# USB_HUB1.net
KiCad netlist of a schematic drawn in Altium Designer
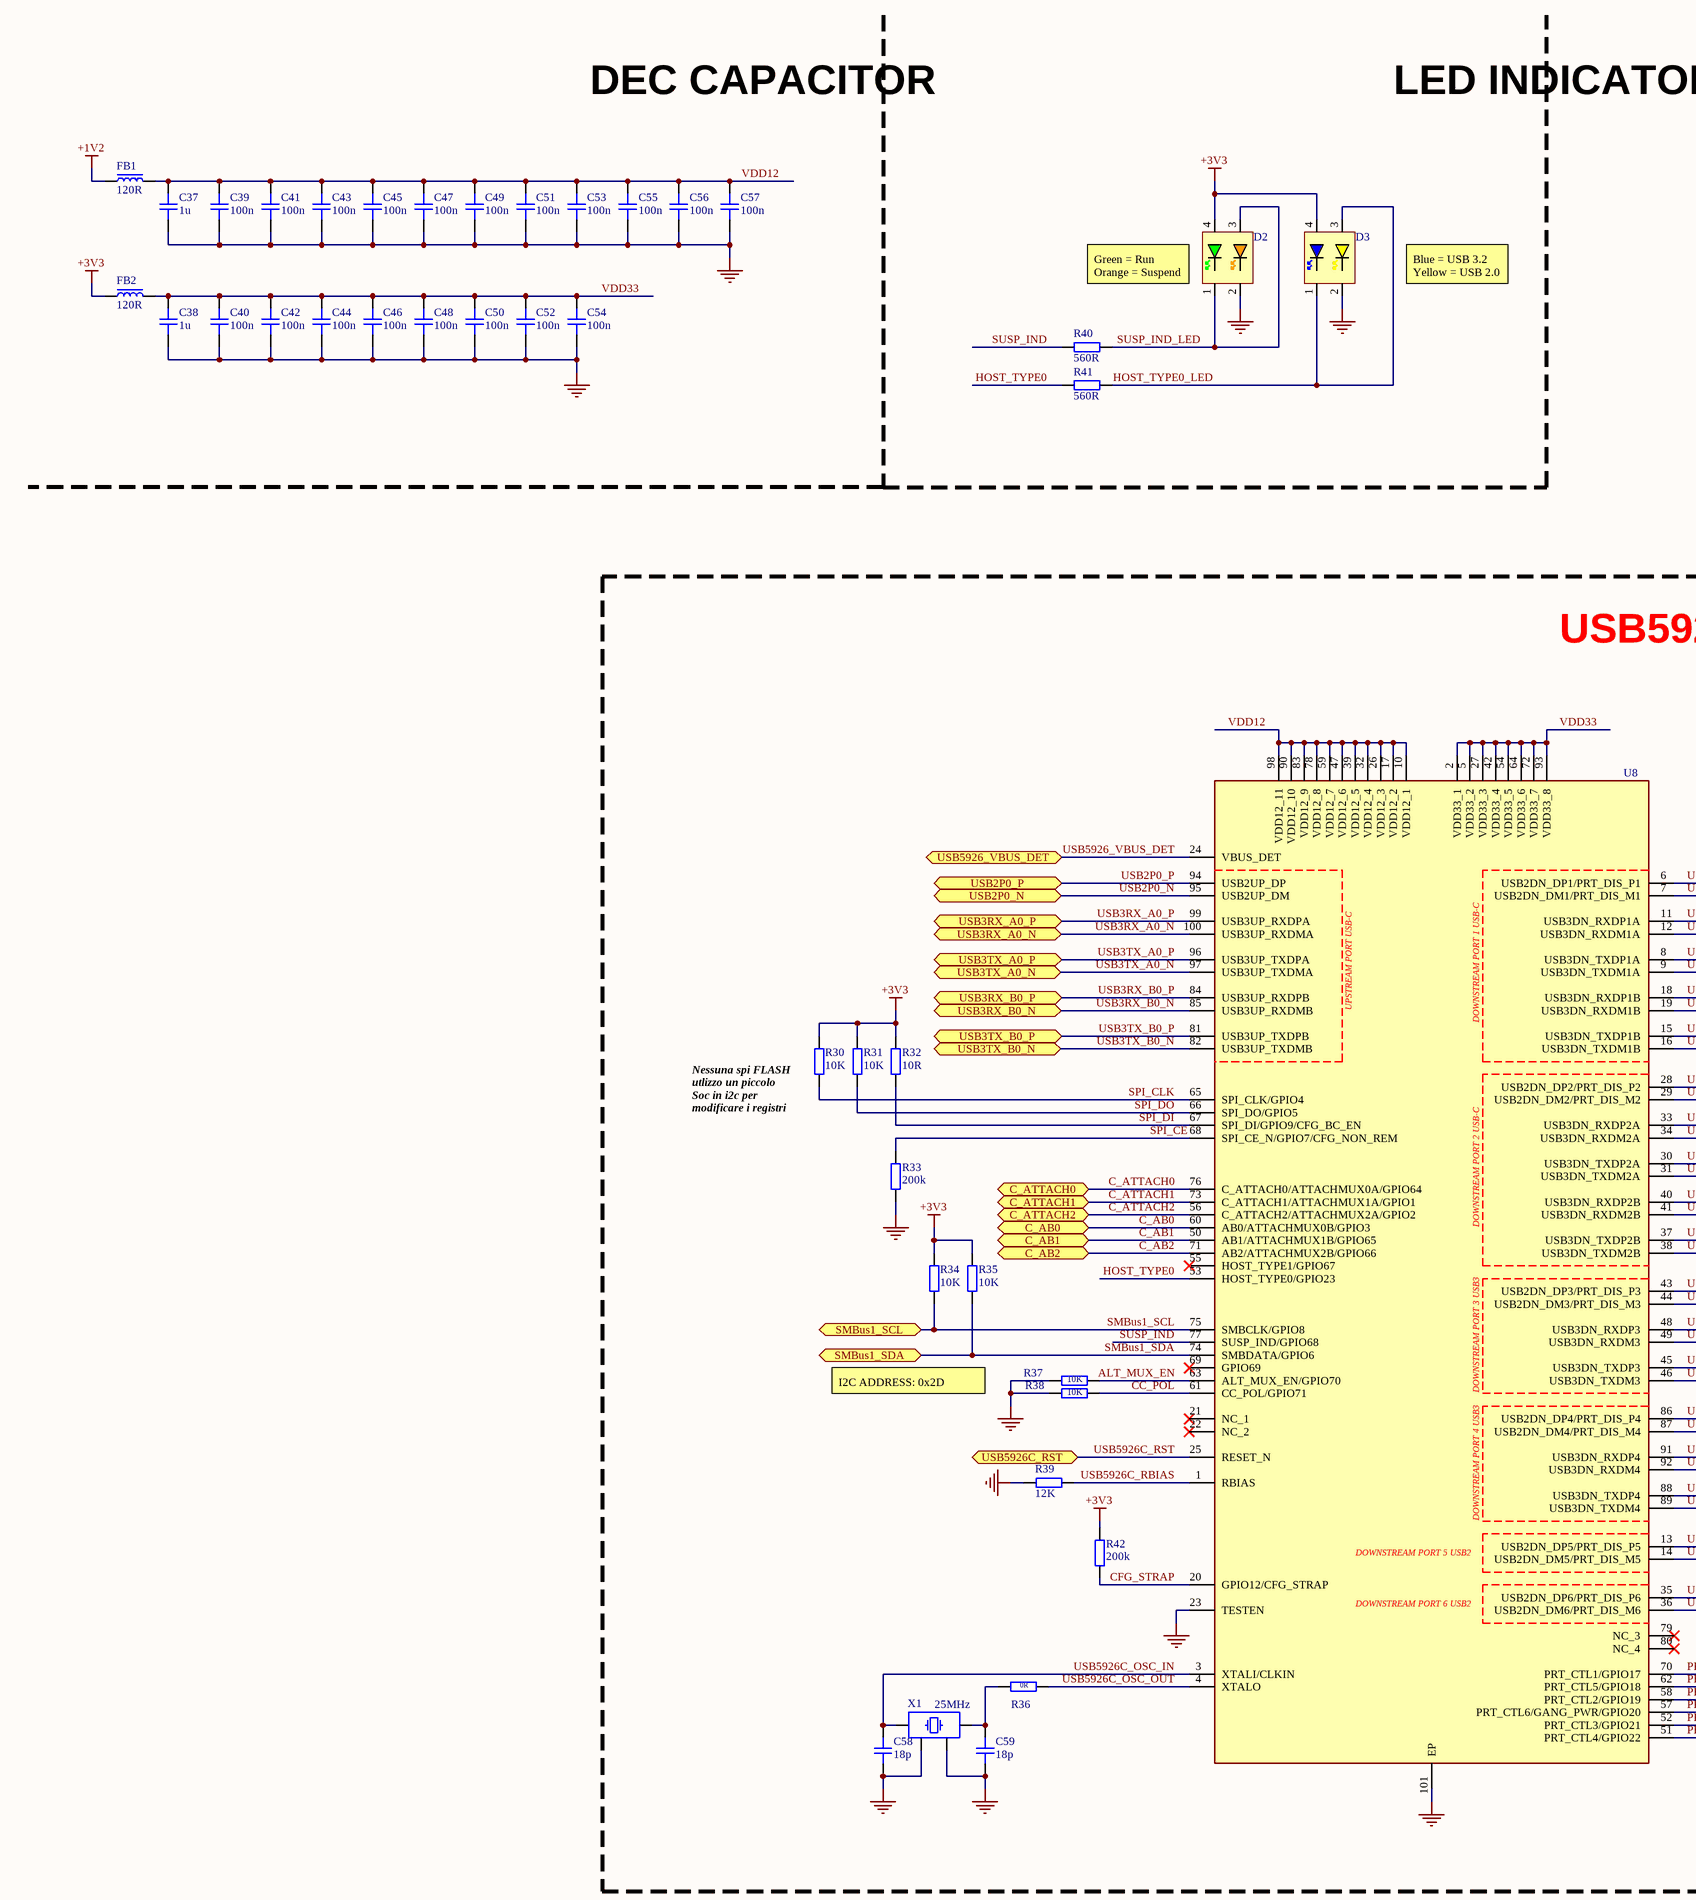
[diagram p0: USB_HUB1.SchDoc, left]
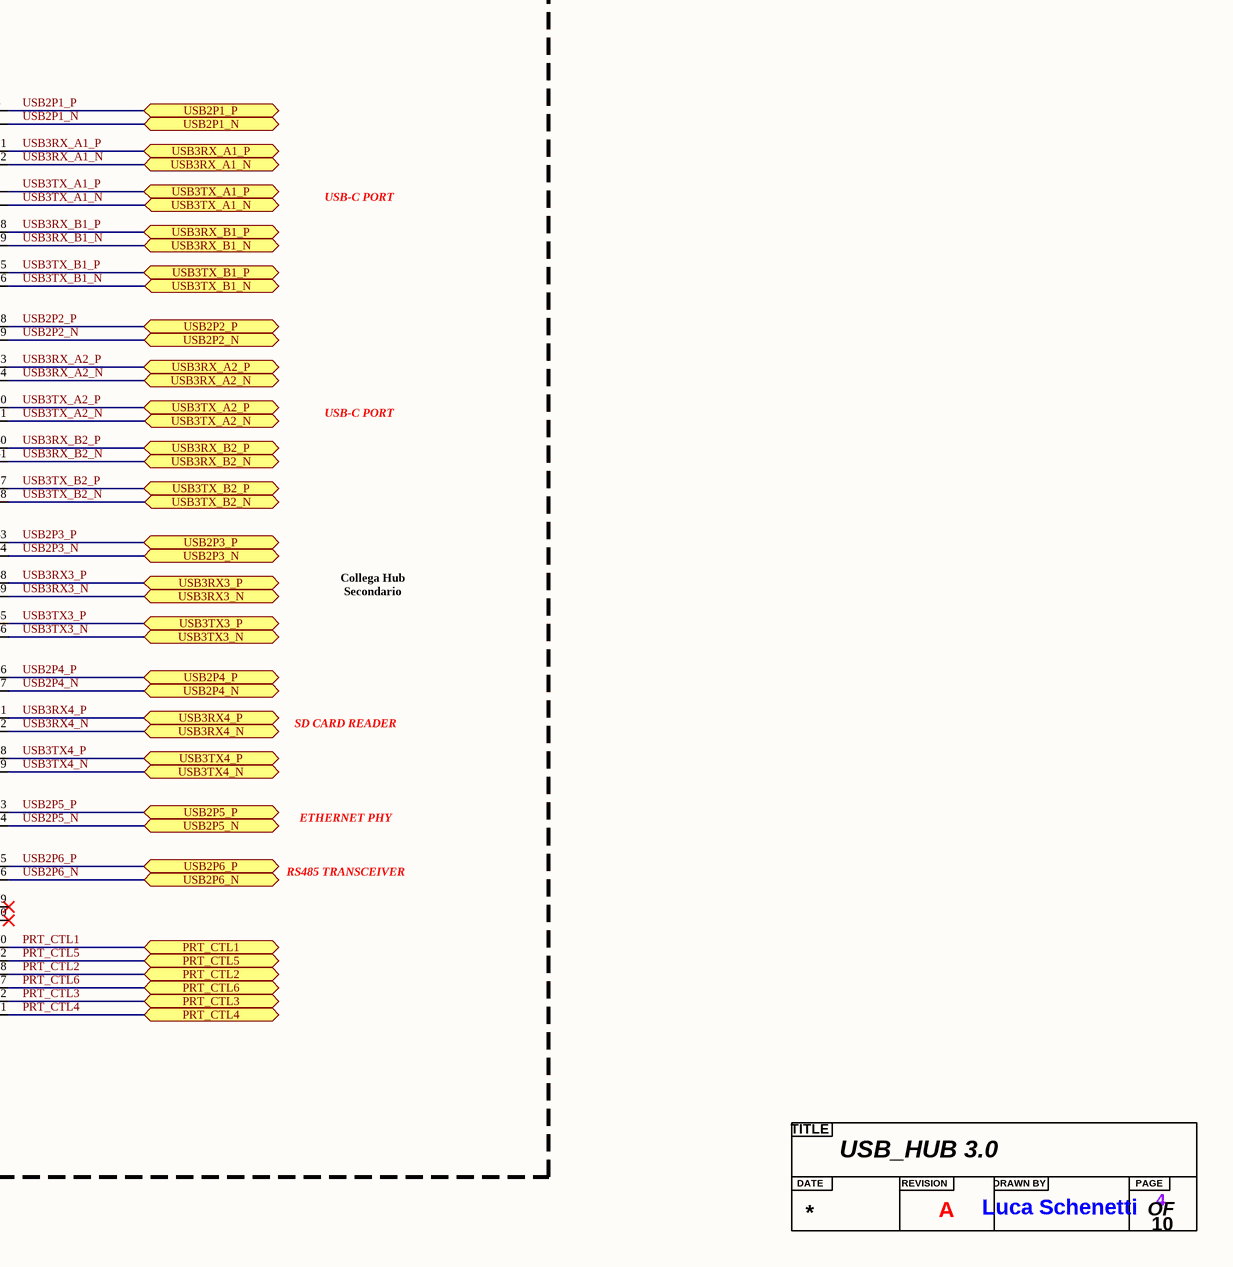
[diagram p1: USB_HUB1.SchDoc, right]

(export (version "E")
  (design (tool "Eeschema 10.0.6"))
  (components
    (comp (ref "C37")
      (value "1u")
      (footprint "CAP_0603")
      (description "Capacitor SMD 0603 [C15849]")
      (libsource (lib "Schematic-Lib-PhilsLab") (part "CAP_0603"))
    )
    (comp (ref "C38")
      (value "1u")
      (footprint "CAP_0603")
      (description "Capacitor SMD 0603 [C15849]")
      (libsource (lib "Schematic-Lib-PhilsLab") (part "CAP_0603"))
    )
    (comp (ref "C39")
      (value "100n")
      (footprint "CAP_0603")
      (description "Capacitor SMD 0603 [C14663]")
      (libsource (lib "Schematic-Lib-PhilsLab") (part "CAP_0603"))
    )
    (comp (ref "C40")
      (value "100n")
      (footprint "CAP_0603")
      (description "Capacitor SMD 0603 [C14663]")
      (libsource (lib "Schematic-Lib-PhilsLab") (part "CAP_0603"))
    )
    (comp (ref "C41")
      (value "100n")
      (footprint "CAP_0603")
      (description "Capacitor SMD 0603 [C14663]")
      (libsource (lib "Schematic-Lib-PhilsLab") (part "CAP_0603"))
    )
    (comp (ref "C42")
      (value "100n")
      (footprint "CAP_0603")
      (description "Capacitor SMD 0603 [C14663]")
      (libsource (lib "Schematic-Lib-PhilsLab") (part "CAP_0603"))
    )
    (comp (ref "C43")
      (value "100n")
      (footprint "CAP_0603")
      (description "Capacitor SMD 0603 [C14663]")
      (libsource (lib "Schematic-Lib-PhilsLab") (part "CAP_0603"))
    )
    (comp (ref "C44")
      (value "100n")
      (footprint "CAP_0603")
      (description "Capacitor SMD 0603 [C14663]")
      (libsource (lib "Schematic-Lib-PhilsLab") (part "CAP_0603"))
    )
    (comp (ref "C45")
      (value "100n")
      (footprint "CAP_0603")
      (description "Capacitor SMD 0603 [C14663]")
      (libsource (lib "Schematic-Lib-PhilsLab") (part "CAP_0603"))
    )
    (comp (ref "C46")
      (value "100n")
      (footprint "CAP_0603")
      (description "Capacitor SMD 0603 [C14663]")
      (libsource (lib "Schematic-Lib-PhilsLab") (part "CAP_0603"))
    )
    (comp (ref "C47")
      (value "100n")
      (footprint "CAP_0603")
      (description "Capacitor SMD 0603 [C14663]")
      (libsource (lib "Schematic-Lib-PhilsLab") (part "CAP_0603"))
    )
    (comp (ref "C48")
      (value "100n")
      (footprint "CAP_0603")
      (description "Capacitor SMD 0603 [C14663]")
      (libsource (lib "Schematic-Lib-PhilsLab") (part "CAP_0603"))
    )
    (comp (ref "C49")
      (value "100n")
      (footprint "CAP_0603")
      (description "Capacitor SMD 0603 [C14663]")
      (libsource (lib "Schematic-Lib-PhilsLab") (part "CAP_0603"))
    )
    (comp (ref "C50")
      (value "100n")
      (footprint "CAP_0603")
      (description "Capacitor SMD 0603 [C14663]")
      (libsource (lib "Schematic-Lib-PhilsLab") (part "CAP_0603"))
    )
    (comp (ref "C51")
      (value "100n")
      (footprint "CAP_0603")
      (description "Capacitor SMD 0603 [C14663]")
      (libsource (lib "Schematic-Lib-PhilsLab") (part "CAP_0603"))
    )
    (comp (ref "C52")
      (value "100n")
      (footprint "CAP_0603")
      (description "Capacitor SMD 0603 [C14663]")
      (libsource (lib "Schematic-Lib-PhilsLab") (part "CAP_0603"))
    )
    (comp (ref "C53")
      (value "100n")
      (footprint "CAP_0603")
      (description "Capacitor SMD 0603 [C14663]")
      (libsource (lib "Schematic-Lib-PhilsLab") (part "CAP_0603"))
    )
    (comp (ref "C54")
      (value "100n")
      (footprint "CAP_0603")
      (description "Capacitor SMD 0603 [C14663]")
      (libsource (lib "Schematic-Lib-PhilsLab") (part "CAP_0603"))
    )
    (comp (ref "C55")
      (value "100n")
      (footprint "CAP_0603")
      (description "Capacitor SMD 0603 [C14663]")
      (libsource (lib "Schematic-Lib-PhilsLab") (part "CAP_0603"))
    )
    (comp (ref "C56")
      (value "100n")
      (footprint "CAP_0603")
      (description "Capacitor SMD 0603 [C14663]")
      (libsource (lib "Schematic-Lib-PhilsLab") (part "CAP_0603"))
    )
    (comp (ref "C57")
      (value "100n")
      (footprint "CAP_0603")
      (description "Capacitor SMD 0603 [C14663]")
      (libsource (lib "Schematic-Lib-PhilsLab") (part "CAP_0603"))
    )
    (comp (ref "C58")
      (value "18p")
      (footprint "CAP_0402")
      (description "Capacitor SMD 0402 [C1549]")
      (libsource (lib "Schematic-Lib-PhilsLab") (part "CAP_0402"))
    )
    (comp (ref "C59")
      (value "18p")
      (footprint "CAP_0402")
      (description "Capacitor SMD 0402 [C1549]")
      (libsource (lib "Schematic-Lib-PhilsLab") (part "CAP_0402"))
    )
    (comp (ref "D2")
      (value "TWO LED Orange Green 0603")
      (footprint "A-SP1962S1GHC-C01-3T")
      (description "[C19171293]")
      (libsource (lib "My_Library") (part "A-SP1962S1GHC-C01-3T"))
    )
    (comp (ref "D3")
      (value "TWO LED Yellow Blue 0603")
      (footprint "A-SP1962Y3B1C-C01-3T")
      (description "[C19171299]")
      (libsource (lib "My_Library") (part "A-SP1962Y3B1C-C01-3T"))
    )
    (comp (ref "FB1")
      (value "120R")
      (footprint "FB_0603")
      (description "Ferrite Bead SMD 0603[C76892]")
      (libsource (lib "Schematic-Lib-PhilsLab") (part "FB_0603"))
    )
    (comp (ref "FB2")
      (value "120R")
      (footprint "FB_0603")
      (description "Ferrite Bead SMD 0603[C76892]")
      (libsource (lib "Schematic-Lib-PhilsLab") (part "FB_0603"))
    )
    (comp (ref "R30")
      (value "10K")
      (footprint "RES_0603")
      (description "Resistor SMD 0603[C25804]")
      (libsource (lib "Schematic-Lib-PhilsLab") (part "RES_0603"))
    )
    (comp (ref "R31")
      (value "10K")
      (footprint "RES_0603")
      (description "Resistor SMD 0603[C25804]")
      (libsource (lib "Schematic-Lib-PhilsLab") (part "RES_0603"))
    )
    (comp (ref "R32")
      (value "10R")
      (footprint "RES_0603")
      (description "Resistor SMD 0603[C22859]")
      (libsource (lib "Schematic-Lib-PhilsLab") (part "RES_0603"))
    )
    (comp (ref "R33")
      (value "200k")
      (footprint "RES_0603")
      (description "Resistor SMD 0603[C25811]")
      (libsource (lib "Schematic-Lib-PhilsLab") (part "RES_0603"))
    )
    (comp (ref "R34")
      (value "10K")
      (footprint "RES_0603")
      (description "Resistor SMD 0603[C25804]")
      (libsource (lib "Schematic-Lib-PhilsLab") (part "RES_0603"))
    )
    (comp (ref "R35")
      (value "10K")
      (footprint "RES_0603")
      (description "Resistor SMD 0603[C25804]")
      (libsource (lib "Schematic-Lib-PhilsLab") (part "RES_0603"))
    )
    (comp (ref "R36")
      (value "0R")
      (footprint "RES_0402")
      (description "Resistor SMD 0402 [C17168]")
      (libsource (lib "Schematic-Lib-PhilsLab") (part "RES_0402"))
    )
    (comp (ref "R37")
      (value "10K")
      (footprint "RES_0603")
      (description "Resistor SMD 0603[C25804]")
      (libsource (lib "Schematic-Lib-PhilsLab") (part "RES_0603"))
    )
    (comp (ref "R38")
      (value "10K")
      (footprint "RES_0603")
      (description "Resistor SMD 0603[C25804]")
      (libsource (lib "Schematic-Lib-PhilsLab") (part "RES_0603"))
    )
    (comp (ref "R39")
      (value "12K")
      (footprint "RES_0603")
      (description "[C22790]")
      (libsource (lib "Schematic-Lib-PhilsLab") (part "RES_0603"))
    )
    (comp (ref "R40")
      (value "560R")
      (footprint "RES_0603")
      (description "[C23204]")
      (libsource (lib "Schematic-Lib-PhilsLab") (part "RES_0603"))
    )
    (comp (ref "R41")
      (value "560R")
      (footprint "RES_0603")
      (description "[C23204]")
      (libsource (lib "Schematic-Lib-PhilsLab") (part "RES_0603"))
    )
    (comp (ref "R42")
      (value "200k")
      (footprint "RES_0603")
      (description "Resistor SMD 0603[C25811]")
      (libsource (lib "Schematic-Lib-PhilsLab") (part "RES_0603"))
    )
    (comp (ref "U8")
      (value "6-Port USB 3.1 Gen 1 Smart Hub")
      (footprint "USB5926C/KD")
      (description "[C3210694]")
      (libsource (lib "My_Library") (part "USB5926C/KD"))
    )
    (comp (ref "X1")
      (value "25MHz")
      (footprint "XTAL_3225")
      (description "Crystal SMD 24MHz 10PPM 7pF 3225 [C9006]")
      (fields
        (field (name "MANUFACTURER") "Epson")
        (field (name "MANUFACTURER PART NUMBER") "TSX-3225 24.0000MF15X-AC")
      )
      (libsource (lib "Schematic-Lib-PhilsLab") (part "TSX-3225_24.0000MF15X-AC"))
    )
  )
  (nets
    (net (code "1") (name "+1V2") (class "Default")
      (node (ref "FB1") (pin "1") (pinfunction "1_1") (pintype "passive"))
    )
    (net (code "2") (name "+3V3") (class "Default")
      (node (ref "D2") (pin "4") (pinfunction "4_4") (pintype "passive"))
      (node (ref "D3") (pin "4") (pinfunction "4_4") (pintype "passive"))
      (node (ref "FB2") (pin "1") (pinfunction "1_1") (pintype "passive"))
      (node (ref "R30") (pin "2") (pinfunction "2_2") (pintype "passive"))
      (node (ref "R31") (pin "2") (pinfunction "2_2") (pintype "passive"))
      (node (ref "R32") (pin "2") (pinfunction "2_2") (pintype "passive"))
      (node (ref "R34") (pin "2") (pinfunction "2_2") (pintype "passive"))
      (node (ref "R35") (pin "2") (pinfunction "2_2") (pintype "passive"))
      (node (ref "R42") (pin "2") (pinfunction "2_2") (pintype "passive"))
    )
    (net (code "3") (name "/ALT_MUX_EN") (class "Default")
      (node (ref "R37") (pin "1") (pinfunction "1_1") (pintype "passive"))
      (node (ref "U8") (pin "63") (pinfunction "ALT_MUX_EN/GPIO70_63") (pintype "passive"))
    )
    (net (code "4") (name "/CC_POL") (class "Default")
      (node (ref "R38") (pin "1") (pinfunction "1_1") (pintype "passive"))
      (node (ref "U8") (pin "61") (pinfunction "CC_POL/GPIO71_61") (pintype "passive"))
    )
    (net (code "5") (name "/CFG_STRAP") (class "Default")
      (node (ref "R42") (pin "1") (pinfunction "1_1") (pintype "passive"))
      (node (ref "U8") (pin "20") (pinfunction "GPIO12/CFG_STRAP_20") (pintype "passive"))
    )
    (net (code "6") (name "/C_AB0") (class "Default")
      (node (ref "U8") (pin "60") (pinfunction "AB0/ATTACHMUX0B/GPIO3_60") (pintype "passive"))
    )
    (net (code "7") (name "/C_AB1") (class "Default")
      (node (ref "U8") (pin "50") (pinfunction "AB1/ATTACHMUX1B/GPIO65_50") (pintype "passive"))
    )
    (net (code "8") (name "/C_AB2") (class "Default")
      (node (ref "U8") (pin "71") (pinfunction "AB2/ATTACHMUX2B/GPIO66_71") (pintype "passive"))
    )
    (net (code "9") (name "/C_ATTACH0") (class "Default")
      (node (ref "U8") (pin "76") (pinfunction "C_ATTACH0/ATTACHMUX0A/GPIO64_76") (pintype "passive"))
    )
    (net (code "10") (name "/C_ATTACH1") (class "Default")
      (node (ref "U8") (pin "73") (pinfunction "C_ATTACH1/ATTACHMUX1A/GPIO1_73") (pintype "passive"))
    )
    (net (code "11") (name "/C_ATTACH2") (class "Default")
      (node (ref "U8") (pin "56") (pinfunction "C_ATTACH2/ATTACHMUX2A/GPIO2_56") (pintype "passive"))
    )
    (net (code "12") (name "/HOST_TYPE0") (class "Default")
      (node (ref "R41") (pin "2") (pinfunction "2_2") (pintype "passive"))
      (node (ref "U8") (pin "53") (pinfunction "HOST_TYPE0/GPIO23_53") (pintype "passive"))
    )
    (net (code "13") (name "/HOST_TYPE0_LED") (class "Default")
      (node (ref "D3") (pin "1") (pinfunction "1_1") (pintype "passive"))
      (node (ref "D3") (pin "3") (pinfunction "3_3") (pintype "passive"))
      (node (ref "R41") (pin "1") (pinfunction "1_1") (pintype "passive"))
    )
    (net (code "14") (name "/PRT_CTL1") (class "Default")
      (node (ref "U8") (pin "70") (pinfunction "PRT_CTL1/GPIO17_70") (pintype "passive"))
    )
    (net (code "15") (name "/PRT_CTL2") (class "Default")
      (node (ref "U8") (pin "58") (pinfunction "PRT_CTL2/GPIO19_58") (pintype "passive"))
    )
    (net (code "16") (name "/PRT_CTL3") (class "Default")
      (node (ref "U8") (pin "52") (pinfunction "PRT_CTL3/GPIO21_52") (pintype "passive"))
    )
    (net (code "17") (name "/PRT_CTL4") (class "Default")
      (node (ref "U8") (pin "51") (pinfunction "PRT_CTL4/GPIO22_51") (pintype "passive"))
    )
    (net (code "18") (name "/PRT_CTL5") (class "Default")
      (node (ref "U8") (pin "62") (pinfunction "PRT_CTL5/GPIO18_62") (pintype "passive"))
    )
    (net (code "19") (name "/PRT_CTL6") (class "Default")
      (node (ref "U8") (pin "57") (pinfunction "PRT_CTL6/GANG_PWR/GPIO20_57") (pintype "passive"))
    )
    (net (code "20") (name "/SMBus1_SCL") (class "Default")
      (node (ref "R34") (pin "1") (pinfunction "1_1") (pintype "passive"))
      (node (ref "U8") (pin "75") (pinfunction "SMBCLK/GPIO8_75") (pintype "passive"))
    )
    (net (code "21") (name "/SMBus1_SDA") (class "Default")
      (node (ref "R35") (pin "1") (pinfunction "1_1") (pintype "passive"))
      (node (ref "U8") (pin "74") (pinfunction "SMBDATA/GPIO6_74") (pintype "passive"))
    )
    (net (code "22") (name "/SPI_CE") (class "Default")
      (node (ref "R33") (pin "2") (pinfunction "2_2") (pintype "passive"))
      (node (ref "U8") (pin "68") (pinfunction "SPI_CE_N/GPIO7/CFG_NON_REM_68") (pintype "passive"))
    )
    (net (code "23") (name "/SPI_CLK") (class "Default")
      (node (ref "R30") (pin "1") (pinfunction "1_1") (pintype "passive"))
      (node (ref "U8") (pin "65") (pinfunction "SPI_CLK/GPIO4_65") (pintype "passive"))
    )
    (net (code "24") (name "/SPI_DI") (class "Default")
      (node (ref "R32") (pin "1") (pinfunction "1_1") (pintype "passive"))
      (node (ref "U8") (pin "67") (pinfunction "SPI_DI/GPIO9/CFG_BC_EN_67") (pintype "passive"))
    )
    (net (code "25") (name "/SPI_DO") (class "Default")
      (node (ref "R31") (pin "1") (pinfunction "1_1") (pintype "passive"))
      (node (ref "U8") (pin "66") (pinfunction "SPI_DO/GPIO5_66") (pintype "passive"))
    )
    (net (code "26") (name "/SUSP_IND") (class "Default")
      (node (ref "R40") (pin "2") (pinfunction "2_2") (pintype "passive"))
      (node (ref "U8") (pin "77") (pinfunction "SUSP_IND/GPIO68_77") (pintype "passive"))
    )
    (net (code "27") (name "/SUSP_IND_LED") (class "Default")
      (node (ref "D2") (pin "1") (pinfunction "1_1") (pintype "passive"))
      (node (ref "D2") (pin "3") (pinfunction "3_3") (pintype "passive"))
      (node (ref "R40") (pin "1") (pinfunction "1_1") (pintype "passive"))
    )
    (net (code "28") (name "/USB2P0_N") (class "Default")
      (node (ref "U8") (pin "95") (pinfunction "USB2UP_DM_95") (pintype "passive"))
    )
    (net (code "29") (name "/USB2P0_P") (class "Default")
      (node (ref "U8") (pin "94") (pinfunction "USB2UP_DP_94") (pintype "passive"))
    )
    (net (code "30") (name "/USB2P1_N") (class "Default")
      (node (ref "U8") (pin "7") (pinfunction "USB2DN_DM1/PRT_DIS_M1_7") (pintype "passive"))
    )
    (net (code "31") (name "/USB2P1_P") (class "Default")
      (node (ref "U8") (pin "6") (pinfunction "USB2DN_DP1/PRT_DIS_P1_6") (pintype "passive"))
    )
    (net (code "32") (name "/USB2P2_N") (class "Default")
      (node (ref "U8") (pin "29") (pinfunction "USB2DN_DM2/PRT_DIS_M2_29") (pintype "passive"))
    )
    (net (code "33") (name "/USB2P2_P") (class "Default")
      (node (ref "U8") (pin "28") (pinfunction "USB2DN_DP2/PRT_DIS_P2_28") (pintype "passive"))
    )
    (net (code "34") (name "/USB2P3_N") (class "Default")
      (node (ref "U8") (pin "44") (pinfunction "USB2DN_DM3/PRT_DIS_M3_44") (pintype "passive"))
    )
    (net (code "35") (name "/USB2P3_P") (class "Default")
      (node (ref "U8") (pin "43") (pinfunction "USB2DN_DP3/PRT_DIS_P3_43") (pintype "passive"))
    )
    (net (code "36") (name "/USB2P4_N") (class "Default")
      (node (ref "U8") (pin "87") (pinfunction "USB2DN_DM4/PRT_DIS_M4_87") (pintype "passive"))
    )
    (net (code "37") (name "/USB2P4_P") (class "Default")
      (node (ref "U8") (pin "86") (pinfunction "USB2DN_DP4/PRT_DIS_P4_86") (pintype "passive"))
    )
    (net (code "38") (name "/USB2P5_N") (class "Default")
      (node (ref "U8") (pin "14") (pinfunction "USB2DN_DM5/PRT_DIS_M5_14") (pintype "passive"))
    )
    (net (code "39") (name "/USB2P5_P") (class "Default")
      (node (ref "U8") (pin "13") (pinfunction "USB2DN_DP5/PRT_DIS_P5_13") (pintype "passive"))
    )
    (net (code "40") (name "/USB2P6_N") (class "Default")
      (node (ref "U8") (pin "36") (pinfunction "USB2DN_DM6/PRT_DIS_M6_36") (pintype "passive"))
    )
    (net (code "41") (name "/USB2P6_P") (class "Default")
      (node (ref "U8") (pin "35") (pinfunction "USB2DN_DP6/PRT_DIS_P6_35") (pintype "passive"))
    )
    (net (code "42") (name "/USB3RX3_N") (class "Default")
      (node (ref "U8") (pin "49") (pinfunction "USB3DN_RXDM3_49") (pintype "passive"))
    )
    (net (code "43") (name "/USB3RX3_P") (class "Default")
      (node (ref "U8") (pin "48") (pinfunction "USB3DN_RXDP3_48") (pintype "passive"))
    )
    (net (code "44") (name "/USB3RX4_N") (class "Default")
      (node (ref "U8") (pin "92") (pinfunction "USB3DN_RXDM4_92") (pintype "passive"))
    )
    (net (code "45") (name "/USB3RX4_P") (class "Default")
      (node (ref "U8") (pin "91") (pinfunction "USB3DN_RXDP4_91") (pintype "passive"))
    )
    (net (code "46") (name "/USB3RX_A0_N") (class "Default")
      (node (ref "U8") (pin "100") (pinfunction "USB3UP_RXDMA_100") (pintype "passive"))
    )
    (net (code "47") (name "/USB3RX_A0_P") (class "Default")
      (node (ref "U8") (pin "99") (pinfunction "USB3UP_RXDPA_99") (pintype "passive"))
    )
    (net (code "48") (name "/USB3RX_A1_N") (class "Default")
      (node (ref "U8") (pin "12") (pinfunction "USB3DN_RXDM1A_12") (pintype "passive"))
    )
    (net (code "49") (name "/USB3RX_A1_P") (class "Default")
      (node (ref "U8") (pin "11") (pinfunction "USB3DN_RXDP1A_11") (pintype "passive"))
    )
    (net (code "50") (name "/USB3RX_A2_N") (class "Default")
      (node (ref "U8") (pin "34") (pinfunction "USB3DN_RXDM2A_34") (pintype "passive"))
    )
    (net (code "51") (name "/USB3RX_A2_P") (class "Default")
      (node (ref "U8") (pin "33") (pinfunction "USB3DN_RXDP2A_33") (pintype "passive"))
    )
    (net (code "52") (name "/USB3RX_B0_N") (class "Default")
      (node (ref "U8") (pin "85") (pinfunction "USB3UP_RXDMB_85") (pintype "passive"))
    )
    (net (code "53") (name "/USB3RX_B0_P") (class "Default")
      (node (ref "U8") (pin "84") (pinfunction "USB3UP_RXDPB_84") (pintype "passive"))
    )
    (net (code "54") (name "/USB3RX_B1_N") (class "Default")
      (node (ref "U8") (pin "19") (pinfunction "USB3DN_RXDM1B_19") (pintype "passive"))
    )
    (net (code "55") (name "/USB3RX_B1_P") (class "Default")
      (node (ref "U8") (pin "18") (pinfunction "USB3DN_RXDP1B_18") (pintype "passive"))
    )
    (net (code "56") (name "/USB3RX_B2_N") (class "Default")
      (node (ref "U8") (pin "41") (pinfunction "USB3DN_RXDM2B_41") (pintype "passive"))
    )
    (net (code "57") (name "/USB3RX_B2_P") (class "Default")
      (node (ref "U8") (pin "40") (pinfunction "USB3DN_RXDP2B_40") (pintype "passive"))
    )
    (net (code "58") (name "/USB3TX3_N") (class "Default")
      (node (ref "U8") (pin "46") (pinfunction "USB3DN_TXDM3_46") (pintype "passive"))
    )
    (net (code "59") (name "/USB3TX3_P") (class "Default")
      (node (ref "U8") (pin "45") (pinfunction "USB3DN_TXDP3_45") (pintype "passive"))
    )
    (net (code "60") (name "/USB3TX4_N") (class "Default")
      (node (ref "U8") (pin "89") (pinfunction "USB3DN_TXDM4_89") (pintype "passive"))
    )
    (net (code "61") (name "/USB3TX4_P") (class "Default")
      (node (ref "U8") (pin "88") (pinfunction "USB3DN_TXDP4_88") (pintype "passive"))
    )
    (net (code "62") (name "/USB3TX_A0_N") (class "Default")
      (node (ref "U8") (pin "97") (pinfunction "USB3UP_TXDMA_97") (pintype "passive"))
    )
    (net (code "63") (name "/USB3TX_A0_P") (class "Default")
      (node (ref "U8") (pin "96") (pinfunction "USB3UP_TXDPA_96") (pintype "passive"))
    )
    (net (code "64") (name "/USB3TX_A1_N") (class "Default")
      (node (ref "U8") (pin "9") (pinfunction "USB3DN_TXDM1A_9") (pintype "passive"))
    )
    (net (code "65") (name "/USB3TX_A1_P") (class "Default")
      (node (ref "U8") (pin "8") (pinfunction "USB3DN_TXDP1A_8") (pintype "passive"))
    )
    (net (code "66") (name "/USB3TX_A2_N") (class "Default")
      (node (ref "U8") (pin "31") (pinfunction "USB3DN_TXDM2A_31") (pintype "passive"))
    )
    (net (code "67") (name "/USB3TX_A2_P") (class "Default")
      (node (ref "U8") (pin "30") (pinfunction "USB3DN_TXDP2A_30") (pintype "passive"))
    )
    (net (code "68") (name "/USB3TX_B0_N") (class "Default")
      (node (ref "U8") (pin "82") (pinfunction "USB3UP_TXDMB_82") (pintype "passive"))
    )
    (net (code "69") (name "/USB3TX_B0_P") (class "Default")
      (node (ref "U8") (pin "81") (pinfunction "USB3UP_TXDPB_81") (pintype "passive"))
    )
    (net (code "70") (name "/USB3TX_B1_N") (class "Default")
      (node (ref "U8") (pin "16") (pinfunction "USB3DN_TXDM1B_16") (pintype "passive"))
    )
    (net (code "71") (name "/USB3TX_B1_P") (class "Default")
      (node (ref "U8") (pin "15") (pinfunction "USB3DN_TXDP1B_15") (pintype "passive"))
    )
    (net (code "72") (name "/USB3TX_B2_N") (class "Default")
      (node (ref "U8") (pin "38") (pinfunction "USB3DN_TXDM2B_38") (pintype "passive"))
    )
    (net (code "73") (name "/USB3TX_B2_P") (class "Default")
      (node (ref "U8") (pin "37") (pinfunction "USB3DN_TXDP2B_37") (pintype "passive"))
    )
    (net (code "74") (name "/USB5926C_OSC_IN") (class "Default")
      (node (ref "C58") (pin "2") (pinfunction "2_2") (pintype "passive"))
      (node (ref "U8") (pin "3") (pinfunction "XTALI/CLKIN_3") (pintype "passive"))
      (node (ref "X1") (pin "3") (pinfunction "3_3") (pintype "passive"))
    )
    (net (code "75") (name "/USB5926C_OSC_OUT") (class "Default")
      (node (ref "R36") (pin "2") (pinfunction "2_2") (pintype "passive"))
      (node (ref "U8") (pin "4") (pinfunction "XTALO_4") (pintype "passive"))
    )
    (net (code "76") (name "/USB5926C_RBIAS") (class "Default")
      (node (ref "R39") (pin "2") (pinfunction "2_2") (pintype "passive"))
      (node (ref "U8") (pin "1") (pinfunction "RBIAS_1") (pintype "passive"))
    )
    (net (code "77") (name "/USB5926C_RST") (class "Default")
      (node (ref "U8") (pin "25") (pinfunction "RESET_N_25") (pintype "passive"))
    )
    (net (code "78") (name "/USB5926_VBUS_DET") (class "Default")
      (node (ref "U8") (pin "24") (pinfunction "VBUS_DET_24") (pintype "passive"))
    )
    (net (code "79") (name "/VDD12") (class "Default")
      (node (ref "C37") (pin "2") (pinfunction "2_2") (pintype "passive"))
      (node (ref "C39") (pin "2") (pinfunction "2_2") (pintype "passive"))
      (node (ref "C41") (pin "2") (pinfunction "2_2") (pintype "passive"))
      (node (ref "C43") (pin "2") (pinfunction "2_2") (pintype "passive"))
      (node (ref "C45") (pin "2") (pinfunction "2_2") (pintype "passive"))
      (node (ref "C47") (pin "2") (pinfunction "2_2") (pintype "passive"))
      (node (ref "C49") (pin "2") (pinfunction "2_2") (pintype "passive"))
      (node (ref "C51") (pin "2") (pinfunction "2_2") (pintype "passive"))
      (node (ref "C53") (pin "2") (pinfunction "2_2") (pintype "passive"))
      (node (ref "C55") (pin "2") (pinfunction "2_2") (pintype "passive"))
      (node (ref "C56") (pin "2") (pinfunction "2_2") (pintype "passive"))
      (node (ref "C57") (pin "2") (pinfunction "2_2") (pintype "passive"))
      (node (ref "FB1") (pin "2") (pinfunction "2_2") (pintype "passive"))
      (node (ref "U8") (pin "10") (pinfunction "VDD12_1_10") (pintype "passive"))
      (node (ref "U8") (pin "17") (pinfunction "VDD12_2_17") (pintype "passive"))
      (node (ref "U8") (pin "26") (pinfunction "VDD12_3_26") (pintype "passive"))
      (node (ref "U8") (pin "32") (pinfunction "VDD12_4_32") (pintype "passive"))
      (node (ref "U8") (pin "39") (pinfunction "VDD12_5_39") (pintype "passive"))
      (node (ref "U8") (pin "47") (pinfunction "VDD12_6_47") (pintype "passive"))
      (node (ref "U8") (pin "59") (pinfunction "VDD12_7_59") (pintype "passive"))
      (node (ref "U8") (pin "78") (pinfunction "VDD12_8_78") (pintype "passive"))
      (node (ref "U8") (pin "83") (pinfunction "VDD12_9_83") (pintype "passive"))
      (node (ref "U8") (pin "90") (pinfunction "VDD12_10_90") (pintype "passive"))
      (node (ref "U8") (pin "98") (pinfunction "VDD12_11_98") (pintype "passive"))
    )
    (net (code "80") (name "/VDD33") (class "Default")
      (node (ref "C38") (pin "2") (pinfunction "2_2") (pintype "passive"))
      (node (ref "C40") (pin "2") (pinfunction "2_2") (pintype "passive"))
      (node (ref "C42") (pin "2") (pinfunction "2_2") (pintype "passive"))
      (node (ref "C44") (pin "2") (pinfunction "2_2") (pintype "passive"))
      (node (ref "C46") (pin "2") (pinfunction "2_2") (pintype "passive"))
      (node (ref "C48") (pin "2") (pinfunction "2_2") (pintype "passive"))
      (node (ref "C50") (pin "2") (pinfunction "2_2") (pintype "passive"))
      (node (ref "C52") (pin "2") (pinfunction "2_2") (pintype "passive"))
      (node (ref "C54") (pin "2") (pinfunction "2_2") (pintype "passive"))
      (node (ref "FB2") (pin "2") (pinfunction "2_2") (pintype "passive"))
      (node (ref "U8") (pin "2") (pinfunction "VDD33_1_2") (pintype "passive"))
      (node (ref "U8") (pin "27") (pinfunction "VDD33_3_27") (pintype "passive"))
      (node (ref "U8") (pin "42") (pinfunction "VDD33_4_42") (pintype "passive"))
      (node (ref "U8") (pin "5") (pinfunction "VDD33_2_5") (pintype "passive"))
      (node (ref "U8") (pin "54") (pinfunction "VDD33_5_54") (pintype "passive"))
      (node (ref "U8") (pin "64") (pinfunction "VDD33_6_64") (pintype "passive"))
      (node (ref "U8") (pin "72") (pinfunction "VDD33_7_72") (pintype "passive"))
      (node (ref "U8") (pin "93") (pinfunction "VDD33_8_93") (pintype "passive"))
    )
    (net (code "81") (name "GND") (class "Default")
      (node (ref "C37") (pin "1") (pinfunction "1_1") (pintype "passive"))
      (node (ref "C38") (pin "1") (pinfunction "1_1") (pintype "passive"))
      (node (ref "C39") (pin "1") (pinfunction "1_1") (pintype "passive"))
      (node (ref "C40") (pin "1") (pinfunction "1_1") (pintype "passive"))
      (node (ref "C41") (pin "1") (pinfunction "1_1") (pintype "passive"))
      (node (ref "C42") (pin "1") (pinfunction "1_1") (pintype "passive"))
      (node (ref "C43") (pin "1") (pinfunction "1_1") (pintype "passive"))
      (node (ref "C44") (pin "1") (pinfunction "1_1") (pintype "passive"))
      (node (ref "C45") (pin "1") (pinfunction "1_1") (pintype "passive"))
      (node (ref "C46") (pin "1") (pinfunction "1_1") (pintype "passive"))
      (node (ref "C47") (pin "1") (pinfunction "1_1") (pintype "passive"))
      (node (ref "C48") (pin "1") (pinfunction "1_1") (pintype "passive"))
      (node (ref "C49") (pin "1") (pinfunction "1_1") (pintype "passive"))
      (node (ref "C50") (pin "1") (pinfunction "1_1") (pintype "passive"))
      (node (ref "C51") (pin "1") (pinfunction "1_1") (pintype "passive"))
      (node (ref "C52") (pin "1") (pinfunction "1_1") (pintype "passive"))
      (node (ref "C53") (pin "1") (pinfunction "1_1") (pintype "passive"))
      (node (ref "C54") (pin "1") (pinfunction "1_1") (pintype "passive"))
      (node (ref "C55") (pin "1") (pinfunction "1_1") (pintype "passive"))
      (node (ref "C56") (pin "1") (pinfunction "1_1") (pintype "passive"))
      (node (ref "C57") (pin "1") (pinfunction "1_1") (pintype "passive"))
      (node (ref "C58") (pin "1") (pinfunction "1_1") (pintype "passive"))
      (node (ref "C59") (pin "1") (pinfunction "1_1") (pintype "passive"))
      (node (ref "D2") (pin "2") (pinfunction "2_2") (pintype "passive"))
      (node (ref "D3") (pin "2") (pinfunction "2_2") (pintype "passive"))
      (node (ref "R33") (pin "1") (pinfunction "1_1") (pintype "passive"))
      (node (ref "R37") (pin "2") (pinfunction "2_2") (pintype "passive"))
      (node (ref "R38") (pin "2") (pinfunction "2_2") (pintype "passive"))
      (node (ref "R39") (pin "1") (pinfunction "1_1") (pintype "passive"))
      (node (ref "U8") (pin "101") (pinfunction "EP_101") (pintype "passive"))
      (node (ref "U8") (pin "23") (pinfunction "TESTEN_23") (pintype "passive"))
      (node (ref "X1") (pin "2") (pinfunction "2_2") (pintype "passive"))
      (node (ref "X1") (pin "4") (pinfunction "4_4") (pintype "passive"))
    )
    (net (code "82") (name "Net-(C59-Pad2)") (class "Default")
      (node (ref "C59") (pin "2") (pinfunction "2_2") (pintype "passive"))
      (node (ref "R36") (pin "1") (pinfunction "1_1") (pintype "passive"))
      (node (ref "X1") (pin "1") (pinfunction "1_1") (pintype "passive"))
    )
    (net (code "83") (name "unconnected-(U8-GPIO69-Pad69)") (class "Default")
      (node (ref "U8") (pin "69") (pinfunction "GPIO69_69") (pintype "passive+no_connect"))
    )
    (net (code "84") (name "unconnected-(U8-HOST_TYPE1{slash}GPIO67-Pad55)") (class "Default")
      (node (ref "U8") (pin "55") (pinfunction "HOST_TYPE1/GPIO67_55") (pintype "passive+no_connect"))
    )
    (net (code "85") (name "unconnected-(U8-NC_1-Pad21)") (class "Default")
      (node (ref "U8") (pin "21") (pinfunction "NC_1_21") (pintype "passive+no_connect"))
    )
    (net (code "86") (name "unconnected-(U8-NC_2-Pad22)") (class "Default")
      (node (ref "U8") (pin "22") (pinfunction "NC_2_22") (pintype "passive+no_connect"))
    )
    (net (code "87") (name "unconnected-(U8-NC_3-Pad79)") (class "Default")
      (node (ref "U8") (pin "79") (pinfunction "NC_3_79") (pintype "passive+no_connect"))
    )
    (net (code "88") (name "unconnected-(U8-NC_4-Pad80)") (class "Default")
      (node (ref "U8") (pin "80") (pinfunction "NC_4_80") (pintype "passive+no_connect"))
    )
  )
)
